# Bit_Alignment_Tester.net
KiCad netlist of a schematic drawn in Altium Designer
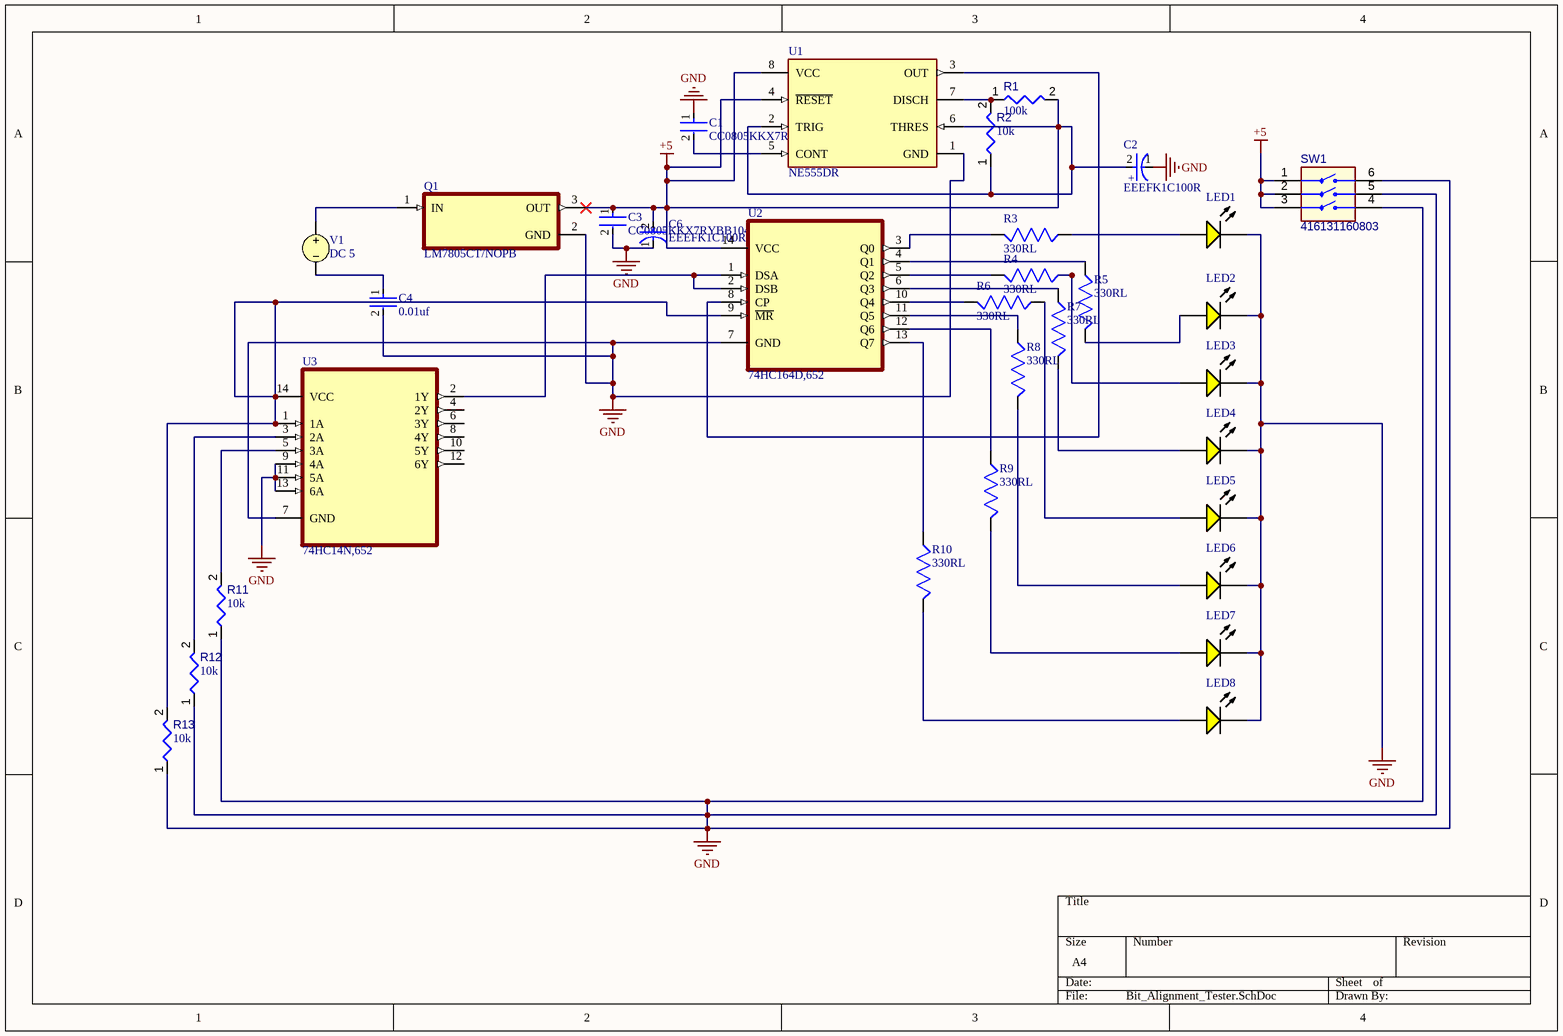
[diagram p0: Bit_Alignment_Tester.SchDoc]

(export (version "E")
  (design (tool "Eeschema 10.0.6"))
  (components
    (comp (ref "C1")
      (value "CC0805KKX7RYBB104")
      (footprint "FP-CC0805-EB-MFG")
      (description "CC0805KKX7RYBB104 Capacitor Ceramic 0.01uF 250V X7R 10% 0805 T/R")
      (fields (field (name "TOLERANCE") "10%"))
      (libsource (lib "Altium Content Vault") (part "b4654b650e69147ec39a6b967a45e02"))
    )
    (comp (ref "C2")
      (value "EEEFK1C100R")
      (footprint "FP-FKB-MFG")
      (description "CAP ALUM 10UF 20% 16V SMD")
      (fields (field (name "VOLTAGE") "16V") (field (name "TOLERANCE") "20%"))
      (libsource (lib "Altium Content Vault") (part "203bc49f2ac43e59fd269a8c329ed05"))
    )
    (comp (ref "C3")
      (value "CC0805KKX7RYBB104")
      (footprint "FP-CC0805-EB-MFG")
      (description "CC0805KKX7RYBB104 Capacitor Ceramic 0.01uF 250V X7R 10% 0805 T/R")
      (fields (field (name "TOLERANCE") "10%"))
      (libsource (lib "Altium Content Vault") (part "b4654b650e69147ec39a6b967a45e02"))
    )
    (comp (ref "C4")
      (value "0.01uf")
      (footprint "FP-CC0805-EB-MFG")
      (description "CC0805KKX7RYBB104 Capacitor Ceramic 0.01uF 250V X7R 10% 0805 T/R")
      (fields (field (name "TOLERANCE") "10%"))
      (libsource (lib "Altium Content Vault") (part "b4654b650e69147ec39a6b967a45e02"))
    )
    (comp (ref "C6")
      (value "EEEFK1C100R")
      (footprint "FP-FKB-MFG")
      (description "CAP ALUM 10UF 20% 16V SMD")
      (fields (field (name "VOLTAGE") "16V") (field (name "TOLERANCE") "20%"))
      (libsource (lib "Altium Content Vault") (part "203bc49f2ac43e59fd269a8c329ed05"))
    )
    (comp (ref "LED1")
      (value "~")
      (footprint "LTST-C190KSKT_V")
      (description "LED Uni-Color Yellow, 75 mW, 30 mA, -30 to 85 degC, 2-Pin SMD, RoHS, Tape and Reel")
      (fields (field (name "MANUFACTURER") "Lite-On") (field (name "POWER") "75mW"))
      (libsource (lib "HARIKRISHNA") (part "LED-YELLOW-AK-2"))
    )
    (comp (ref "LED2")
      (value "~")
      (footprint "LTST-C190KSKT_V")
      (description "LED Uni-Color Yellow, 75 mW, 30 mA, -30 to 85 degC, 2-Pin SMD, RoHS, Tape and Reel")
      (fields (field (name "MANUFACTURER") "Lite-On") (field (name "POWER") "75mW"))
      (libsource (lib "HARIKRISHNA") (part "LED-YELLOW-AK-2"))
    )
    (comp (ref "LED3")
      (value "~")
      (footprint "LTST-C190KSKT_V")
      (description "LED Uni-Color Yellow, 75 mW, 30 mA, -30 to 85 degC, 2-Pin SMD, RoHS, Tape and Reel")
      (fields (field (name "MANUFACTURER") "Lite-On") (field (name "POWER") "75mW"))
      (libsource (lib "HARIKRISHNA") (part "LED-YELLOW-AK-2"))
    )
    (comp (ref "LED4")
      (value "~")
      (footprint "LTST-C190KSKT_V")
      (description "LED Uni-Color Yellow, 75 mW, 30 mA, -30 to 85 degC, 2-Pin SMD, RoHS, Tape and Reel")
      (fields (field (name "MANUFACTURER") "Lite-On") (field (name "POWER") "75mW"))
      (libsource (lib "HARIKRISHNA") (part "LED-YELLOW-AK-2"))
    )
    (comp (ref "LED5")
      (value "~")
      (footprint "LTST-C190KSKT_V")
      (description "LED Uni-Color Yellow, 75 mW, 30 mA, -30 to 85 degC, 2-Pin SMD, RoHS, Tape and Reel")
      (fields (field (name "MANUFACTURER") "Lite-On") (field (name "POWER") "75mW"))
      (libsource (lib "HARIKRISHNA") (part "LED-YELLOW-AK-2"))
    )
    (comp (ref "LED6")
      (value "~")
      (footprint "LTST-C190KSKT_V")
      (description "LED Uni-Color Yellow, 75 mW, 30 mA, -30 to 85 degC, 2-Pin SMD, RoHS, Tape and Reel")
      (fields (field (name "MANUFACTURER") "Lite-On") (field (name "POWER") "75mW"))
      (libsource (lib "HARIKRISHNA") (part "LED-YELLOW-AK-2"))
    )
    (comp (ref "LED7")
      (value "~")
      (footprint "LTST-C190KSKT_V")
      (description "LED Uni-Color Yellow, 75 mW, 30 mA, -30 to 85 degC, 2-Pin SMD, RoHS, Tape and Reel")
      (fields (field (name "MANUFACTURER") "Lite-On") (field (name "POWER") "75mW"))
      (libsource (lib "HARIKRISHNA") (part "LED-YELLOW-AK-2"))
    )
    (comp (ref "LED8")
      (value "~")
      (footprint "LTST-C190KSKT_V")
      (description "LED Uni-Color Yellow, 75 mW, 30 mA, -30 to 85 degC, 2-Pin SMD, RoHS, Tape and Reel")
      (fields (field (name "MANUFACTURER") "Lite-On") (field (name "POWER") "75mW"))
      (libsource (lib "HARIKRISHNA") (part "LED-YELLOW-AK-2"))
    )
    (comp (ref "Q1")
      (value "LM7805CT/NOPB")
      (footprint "TO254P1054X470X1955-3")
      (fields (field (name "MF") "{'manufacturer': u'Texas Instruments'}"))
      (libsource (lib "LM7805CT_NOPB") (part "LM7805CT/NOPB"))
    )
    (comp (ref "R1")
      (value "100k")
      (footprint "RESC0402(1005)_L")
      (description "Chip Resistor, 100 kOhms, +/-1 %, 63 mW, -55 to 155 degC, 0402")
      (fields (field (name "TOLERANCE") "1%") (field (name "POWER") "63mW"))
      (libsource (lib "HARIKRISHNA") (part "RES-2"))
    )
    (comp (ref "R2")
      (value "10k")
      (footprint "RESC0402(1005)_L")
      (description "Chip Resistor, 10 kOhms, +/-1 %, 63 mW, -55 to 125 degC, 0402")
      (fields (field (name "POWER") "63mW") (field (name "TOLERANCE") "1%"))
      (libsource (lib "HARIKRISHNA") (part "RES-2"))
    )
    (comp (ref "R3")
      (value "330RL")
      (footprint "RESC2012X60N")
      (fields (field (name "MP") "RC0805FR-7W330RL"))
      (libsource (lib "RC0805FR-7W330RL") (part "RC0805FR-7W330RL"))
    )
    (comp (ref "R4")
      (value "330RL")
      (footprint "RESC2012X60N")
      (fields (field (name "MP") "RC0805FR-7W330RL"))
      (libsource (lib "RC0805FR-7W330RL") (part "RC0805FR-7W330RL"))
    )
    (comp (ref "R5")
      (value "330RL")
      (footprint "RESC2012X60N")
      (fields (field (name "MP") "RC0805FR-7W330RL"))
      (libsource (lib "RC0805FR-7W330RL") (part "RC0805FR-7W330RL"))
    )
    (comp (ref "R6")
      (value "330RL")
      (footprint "RESC2012X60N")
      (fields (field (name "MP") "RC0805FR-7W330RL"))
      (libsource (lib "RC0805FR-7W330RL") (part "RC0805FR-7W330RL"))
    )
    (comp (ref "R7")
      (value "330RL")
      (footprint "RESC2012X60N")
      (fields (field (name "MP") "RC0805FR-7W330RL"))
      (libsource (lib "RC0805FR-7W330RL") (part "RC0805FR-7W330RL"))
    )
    (comp (ref "R8")
      (value "330RL")
      (footprint "RESC2012X60N")
      (fields (field (name "MP") "RC0805FR-7W330RL"))
      (libsource (lib "RC0805FR-7W330RL") (part "RC0805FR-7W330RL"))
    )
    (comp (ref "R9")
      (value "330RL")
      (footprint "RESC2012X60N")
      (fields (field (name "MP") "RC0805FR-7W330RL"))
      (libsource (lib "RC0805FR-7W330RL") (part "RC0805FR-7W330RL"))
    )
    (comp (ref "R10")
      (value "330RL")
      (footprint "RESC2012X60N")
      (fields (field (name "MP") "RC0805FR-7W330RL"))
      (libsource (lib "RC0805FR-7W330RL") (part "RC0805FR-7W330RL"))
    )
    (comp (ref "R11")
      (value "10k")
      (footprint "RESC0402(1005)_L")
      (description "Chip Resistor, 10 kOhms, +/-1 %, 63 mW, -55 to 125 degC, 0402")
      (fields (field (name "POWER") "63mW") (field (name "TOLERANCE") "1%"))
      (libsource (lib "HARIKRISHNA") (part "RES-2"))
    )
    (comp (ref "R12")
      (value "10k")
      (footprint "RESC0402(1005)_L")
      (description "Chip Resistor, 10 kOhms, +/-1 %, 63 mW, -55 to 125 degC, 0402")
      (fields (field (name "POWER") "63mW") (field (name "TOLERANCE") "1%"))
      (libsource (lib "HARIKRISHNA") (part "RES-2"))
    )
    (comp (ref "R13")
      (value "10k")
      (footprint "RESC0402(1005)_L")
      (description "Chip Resistor, 10 kOhms, +/-1 %, 63 mW, -55 to 125 degC, 0402")
      (fields (field (name "POWER") "63mW") (field (name "TOLERANCE") "1%"))
      (libsource (lib "HARIKRISHNA") (part "RES-2"))
    )
    (comp (ref "SW1")
      (value "416131160803")
      (footprint "416131160803")
      (description "WS-DISV 1.27 mm small compact SMD Dip Switch with top tape")
      (libsource (lib "HARIKRISHNA") (part "CMP-00567-2"))
    )
    (comp (ref "U1")
      (value "NE555DR")
      (footprint "FP-D0008A-IPC_A")
      (description "IC OSC SGL TIMER 100KHZ 8-SOIC")
      (libsource (lib "Altium Content Vault") (part "a29bba90211dec1890110b94dad7d53"))
    )
    (comp (ref "U2")
      (value "74HC164D,652")
      (footprint "SOIC127P600X175-14N")
      (description "Shift Shift Register 1 Element 8 Bit 14-SO")
      (fields (field (name "MF") "Nexperia USA Inc."))
      (libsource (lib "74HC164D,652") (part "74HC164D,652"))
    )
    (comp (ref "U3")
      (value "74HC14N,652")
      (footprint "DIP254P762X420-14")
      (description "Inverter IC 6 Channel Schmitt Trigger 14-DIP")
      (fields (field (name "MF") "NXP USA"))
      (libsource (lib "74HC14N,652") (part "74HC14N,652"))
    )
    (comp (ref "V1")
      (value "DC 5")
      (description "Voltage Source")
      (fields (field (name "PUBLISHER") "Altium Limited"))
      (libsource (lib "Simulation Generic Components") (part "VSRC"))
    )
  )
  (nets
    (net (code "1") (name "+5") (class "Default")
      (node (ref "C2") (pin "2") (pinfunction "A_2") (pintype "passive"))
      (node (ref "C3") (pin "1") (pinfunction "1_1") (pintype "passive"))
      (node (ref "C6") (pin "2") (pinfunction "A_2") (pintype "passive"))
      (node (ref "Q1") (pin "3") (pinfunction "OUT_3") (pintype "output"))
      (node (ref "R1") (pin "2") (pinfunction "2_2") (pintype "passive"))
      (node (ref "R2") (pin "1") (pinfunction "1_1") (pintype "passive"))
      (node (ref "SW1") (pin "1") (pinfunction "1_1") (pintype "passive"))
      (node (ref "SW1") (pin "2") (pinfunction "2_2") (pintype "passive"))
      (node (ref "SW1") (pin "3") (pinfunction "3_3") (pintype "passive"))
      (node (ref "U1") (pin "2") (pinfunction "TRIG_2") (pintype "input"))
      (node (ref "U1") (pin "4") (pinfunction "~{RESET}_4") (pintype "input"))
      (node (ref "U1") (pin "6") (pinfunction "THRES_6") (pintype "input"))
      (node (ref "U1") (pin "8") (pinfunction "VCC_8") (pintype "power_in"))
      (node (ref "U2") (pin "14") (pinfunction "VCC_14") (pintype "power_in"))
    )
    (net (code "2") (name "GND") (class "Default")
      (node (ref "C1") (pin "1") (pinfunction "1_1") (pintype "passive"))
      (node (ref "C2") (pin "1") (pinfunction "C_1") (pintype "passive"))
      (node (ref "C3") (pin "2") (pinfunction "2_2") (pintype "passive"))
      (node (ref "C4") (pin "2") (pinfunction "2_2") (pintype "passive"))
      (node (ref "C6") (pin "1") (pinfunction "C_1") (pintype "passive"))
      (node (ref "LED1") (pin "2") (pinfunction "K_2") (pintype "passive"))
      (node (ref "LED2") (pin "2") (pinfunction "K_2") (pintype "passive"))
      (node (ref "LED3") (pin "2") (pinfunction "K_2") (pintype "passive"))
      (node (ref "LED4") (pin "2") (pinfunction "K_2") (pintype "passive"))
      (node (ref "LED5") (pin "2") (pinfunction "K_2") (pintype "passive"))
      (node (ref "LED6") (pin "2") (pinfunction "K_2") (pintype "passive"))
      (node (ref "LED7") (pin "2") (pinfunction "K_2") (pintype "passive"))
      (node (ref "LED8") (pin "2") (pinfunction "K_2") (pintype "passive"))
      (node (ref "Q1") (pin "2") (pinfunction "GND_2") (pintype "power_in"))
      (node (ref "R11") (pin "1") (pinfunction "1_1") (pintype "passive"))
      (node (ref "R12") (pin "1") (pinfunction "1_1") (pintype "passive"))
      (node (ref "R13") (pin "1") (pinfunction "1_1") (pintype "passive"))
      (node (ref "SW1") (pin "4") (pinfunction "4_4") (pintype "passive"))
      (node (ref "SW1") (pin "5") (pinfunction "5_5") (pintype "passive"))
      (node (ref "SW1") (pin "6") (pinfunction "6_6") (pintype "passive"))
      (node (ref "U1") (pin "1") (pinfunction "GND_1") (pintype "power_in"))
      (node (ref "U2") (pin "7") (pinfunction "GND_7") (pintype "passive"))
      (node (ref "U3") (pin "11") (pinfunction "5A_11") (pintype "input"))
      (node (ref "U3") (pin "13") (pinfunction "6A_13") (pintype "input"))
      (node (ref "U3") (pin "7") (pinfunction "GND_7") (pintype "passive"))
      (node (ref "U3") (pin "9") (pinfunction "4A_9") (pintype "input"))
    )
    (net (code "3") (name "Net-(C4-Pad1)") (class "Default")
      (node (ref "C4") (pin "1") (pinfunction "1_1") (pintype "passive"))
      (node (ref "V1") (pin "2") (pinfunction "2_2") (pintype "passive"))
    )
    (net (code "4") (name "Net-(LED1-A)") (class "Default")
      (node (ref "LED1") (pin "1") (pinfunction "A_1") (pintype "passive"))
      (node (ref "R3") (pin "2") (pinfunction "2_2") (pintype "passive"))
    )
    (net (code "5") (name "Net-(LED2-A)") (class "Default")
      (node (ref "LED2") (pin "1") (pinfunction "A_1") (pintype "passive"))
      (node (ref "R5") (pin "1") (pinfunction "1_1") (pintype "passive"))
    )
    (net (code "6") (name "Net-(LED3-A)") (class "Default")
      (node (ref "LED3") (pin "1") (pinfunction "A_1") (pintype "passive"))
      (node (ref "R4") (pin "2") (pinfunction "2_2") (pintype "passive"))
    )
    (net (code "7") (name "Net-(LED4-A)") (class "Default")
      (node (ref "LED4") (pin "1") (pinfunction "A_1") (pintype "passive"))
      (node (ref "R7") (pin "1") (pinfunction "1_1") (pintype "passive"))
    )
    (net (code "8") (name "Net-(LED5-A)") (class "Default")
      (node (ref "LED5") (pin "1") (pinfunction "A_1") (pintype "passive"))
      (node (ref "R6") (pin "2") (pinfunction "2_2") (pintype "passive"))
    )
    (net (code "9") (name "Net-(LED6-A)") (class "Default")
      (node (ref "LED6") (pin "1") (pinfunction "A_1") (pintype "passive"))
      (node (ref "R8") (pin "1") (pinfunction "1_1") (pintype "passive"))
    )
    (net (code "10") (name "Net-(LED7-A)") (class "Default")
      (node (ref "LED7") (pin "1") (pinfunction "A_1") (pintype "passive"))
      (node (ref "R9") (pin "1") (pinfunction "1_1") (pintype "passive"))
    )
    (net (code "11") (name "Net-(LED8-A)") (class "Default")
      (node (ref "LED8") (pin "1") (pinfunction "A_1") (pintype "passive"))
      (node (ref "R10") (pin "1") (pinfunction "1_1") (pintype "passive"))
    )
    (net (code "12") (name "Net-(Q1-IN)") (class "Default")
      (node (ref "Q1") (pin "1") (pinfunction "IN_1") (pintype "input"))
      (node (ref "V1") (pin "1") (pinfunction "1_1") (pintype "passive"))
    )
    (net (code "13") (name "Net-(U1-CONT)") (class "Default")
      (node (ref "C1") (pin "2") (pinfunction "2_2") (pintype "passive"))
      (node (ref "U1") (pin "5") (pinfunction "CONT_5") (pintype "input"))
    )
    (net (code "14") (name "Net-(U1-DISCH)") (class "Default")
      (node (ref "R1") (pin "1") (pinfunction "1_1") (pintype "passive"))
      (node (ref "R2") (pin "2") (pinfunction "2_2") (pintype "passive"))
      (node (ref "U1") (pin "7") (pinfunction "DISCH_7") (pintype "open_collector"))
    )
    (net (code "15") (name "Net-(U1-OUT)") (class "Default")
      (node (ref "U1") (pin "3") (pinfunction "OUT_3") (pintype "output"))
      (node (ref "U2") (pin "8") (pinfunction "CP_8") (pintype "input"))
    )
    (net (code "16") (name "Net-(U2-DSA)") (class "Default")
      (node (ref "U2") (pin "1") (pinfunction "DSA_1") (pintype "input"))
      (node (ref "U2") (pin "2") (pinfunction "DSB_2") (pintype "input"))
      (node (ref "U3") (pin "2") (pinfunction "1Y_2") (pintype "output"))
    )
    (net (code "17") (name "Net-(U2-Q0)") (class "Default")
      (node (ref "R3") (pin "1") (pinfunction "1_1") (pintype "passive"))
      (node (ref "U2") (pin "3") (pinfunction "Q0_3") (pintype "output"))
    )
    (net (code "18") (name "Net-(U2-Q1)") (class "Default")
      (node (ref "R5") (pin "2") (pinfunction "2_2") (pintype "passive"))
      (node (ref "U2") (pin "4") (pinfunction "Q1_4") (pintype "output"))
    )
    (net (code "19") (name "Net-(U2-Q2)") (class "Default")
      (node (ref "R4") (pin "1") (pinfunction "1_1") (pintype "passive"))
      (node (ref "U2") (pin "5") (pinfunction "Q2_5") (pintype "output"))
    )
    (net (code "20") (name "Net-(U2-Q3)") (class "Default")
      (node (ref "R7") (pin "2") (pinfunction "2_2") (pintype "passive"))
      (node (ref "U2") (pin "6") (pinfunction "Q3_6") (pintype "output"))
    )
    (net (code "21") (name "Net-(U2-Q4)") (class "Default")
      (node (ref "R6") (pin "1") (pinfunction "1_1") (pintype "passive"))
      (node (ref "U2") (pin "10") (pinfunction "Q4_10") (pintype "output"))
    )
    (net (code "22") (name "Net-(U2-Q5)") (class "Default")
      (node (ref "R8") (pin "2") (pinfunction "2_2") (pintype "passive"))
      (node (ref "U2") (pin "11") (pinfunction "Q5_11") (pintype "output"))
    )
    (net (code "23") (name "Net-(U2-Q6)") (class "Default")
      (node (ref "R9") (pin "2") (pinfunction "2_2") (pintype "passive"))
      (node (ref "U2") (pin "12") (pinfunction "Q6_12") (pintype "output"))
    )
    (net (code "24") (name "Net-(U2-Q7)") (class "Default")
      (node (ref "R10") (pin "2") (pinfunction "2_2") (pintype "passive"))
      (node (ref "U2") (pin "13") (pinfunction "Q7_13") (pintype "output"))
    )
    (net (code "25") (name "Net-(U2-~{MR})") (class "Default")
      (node (ref "R13") (pin "2") (pinfunction "2_2") (pintype "passive"))
      (node (ref "U2") (pin "9") (pinfunction "~{MR}_9") (pintype "input"))
      (node (ref "U3") (pin "1") (pinfunction "1A_1") (pintype "input"))
      (node (ref "U3") (pin "14") (pinfunction "VCC_14") (pintype "power_in"))
    )
    (net (code "26") (name "Net-(U3-2A)") (class "Default")
      (node (ref "R12") (pin "2") (pinfunction "2_2") (pintype "passive"))
      (node (ref "U3") (pin "3") (pinfunction "2A_3") (pintype "input"))
    )
    (net (code "27") (name "Net-(U3-3A)") (class "Default")
      (node (ref "R11") (pin "2") (pinfunction "2_2") (pintype "passive"))
      (node (ref "U3") (pin "5") (pinfunction "3A_5") (pintype "input"))
    )
    (net (code "28") (name "unconnected-(U3-2Y-Pad4)") (class "Default")
      (node (ref "U3") (pin "4") (pinfunction "2Y_4") (pintype "output"))
    )
    (net (code "29") (name "unconnected-(U3-3Y-Pad6)") (class "Default")
      (node (ref "U3") (pin "6") (pinfunction "3Y_6") (pintype "output"))
    )
    (net (code "30") (name "unconnected-(U3-4Y-Pad8)") (class "Default")
      (node (ref "U3") (pin "8") (pinfunction "4Y_8") (pintype "output"))
    )
    (net (code "31") (name "unconnected-(U3-5Y-Pad10)") (class "Default")
      (node (ref "U3") (pin "10") (pinfunction "5Y_10") (pintype "output"))
    )
    (net (code "32") (name "unconnected-(U3-6Y-Pad12)") (class "Default")
      (node (ref "U3") (pin "12") (pinfunction "6Y_12") (pintype "output"))
    )
  )
)
